# tms9918.net
KiCad netlist of a schematic drawn in EAGLE
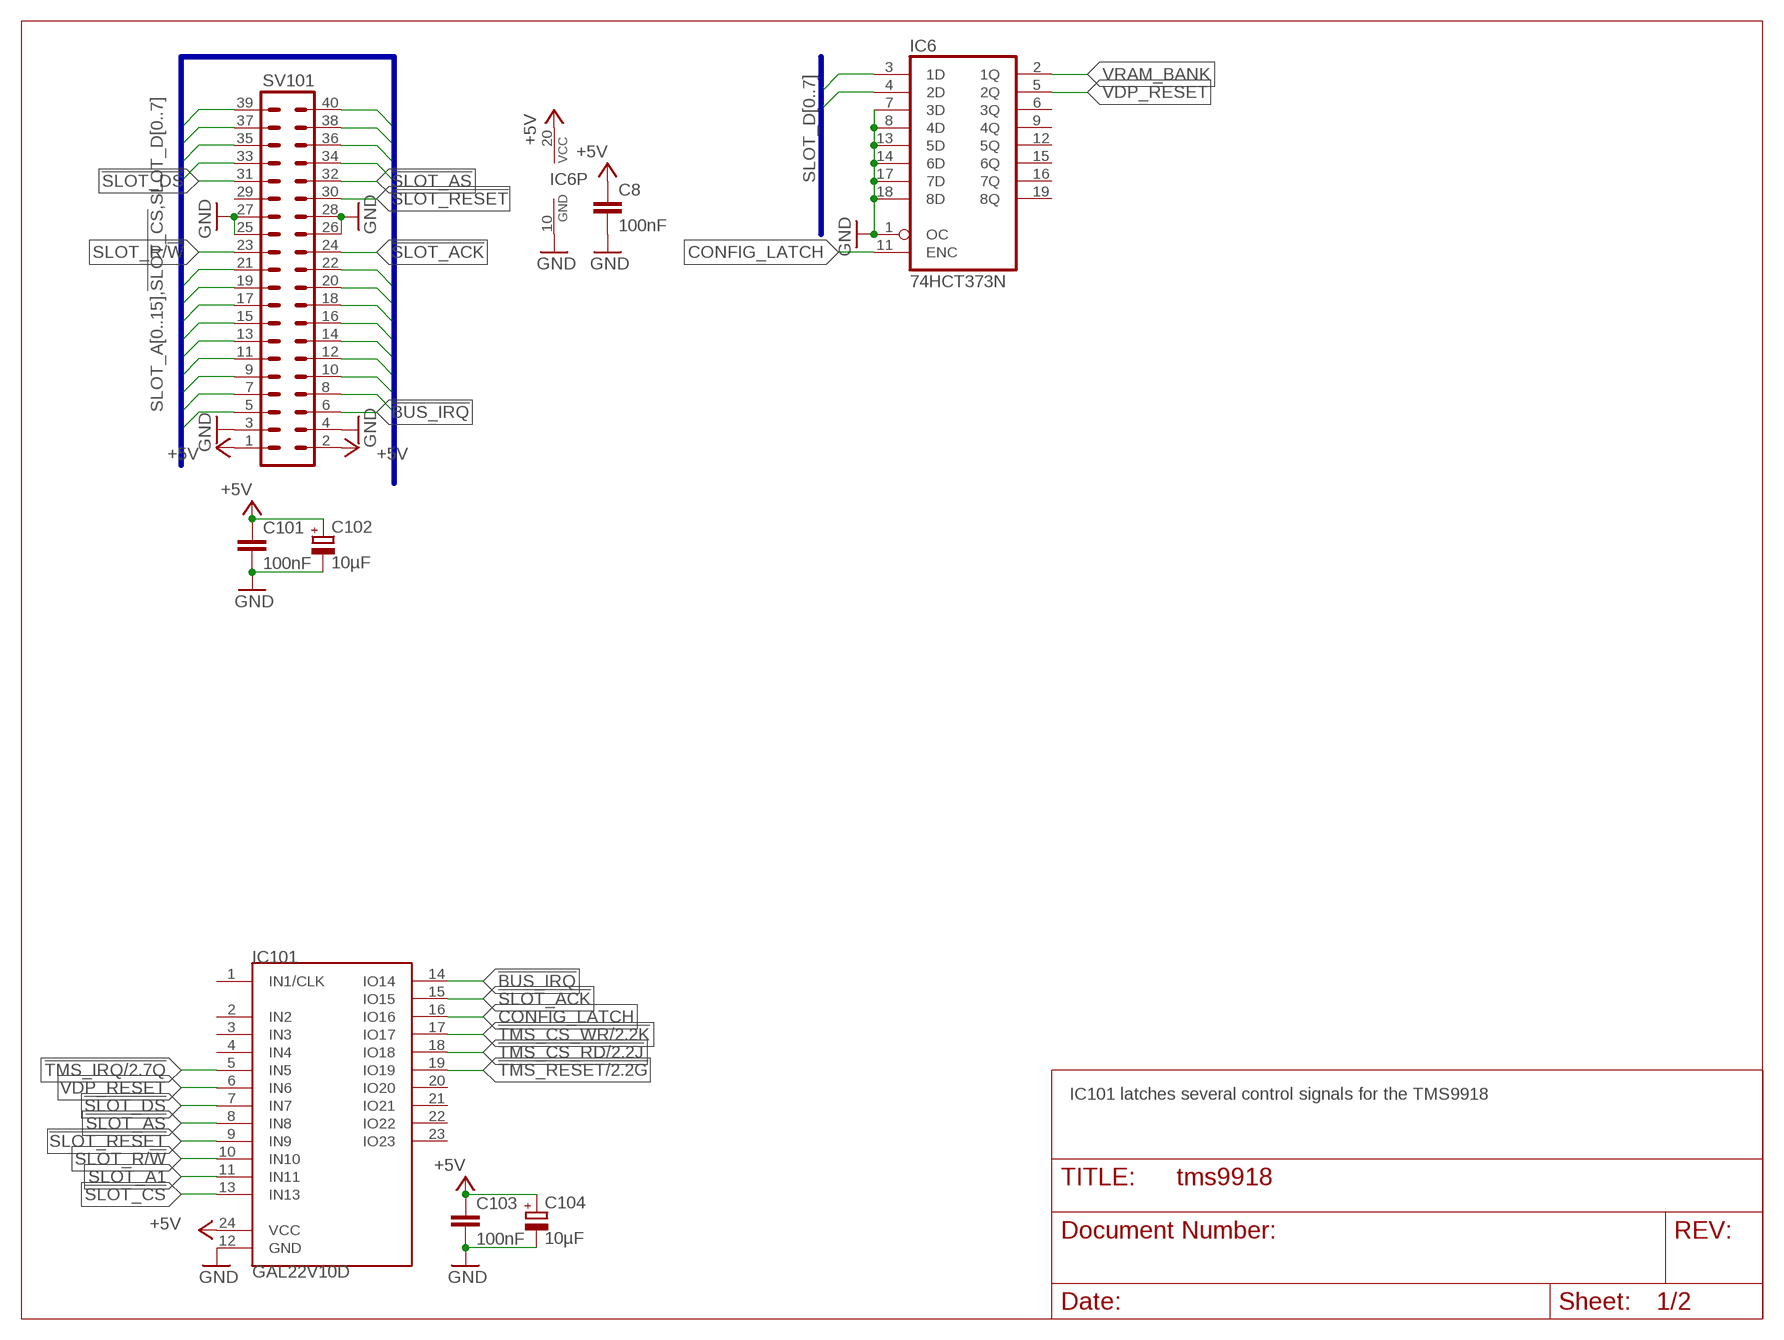
[diagram p0: schematic, sheet 1]
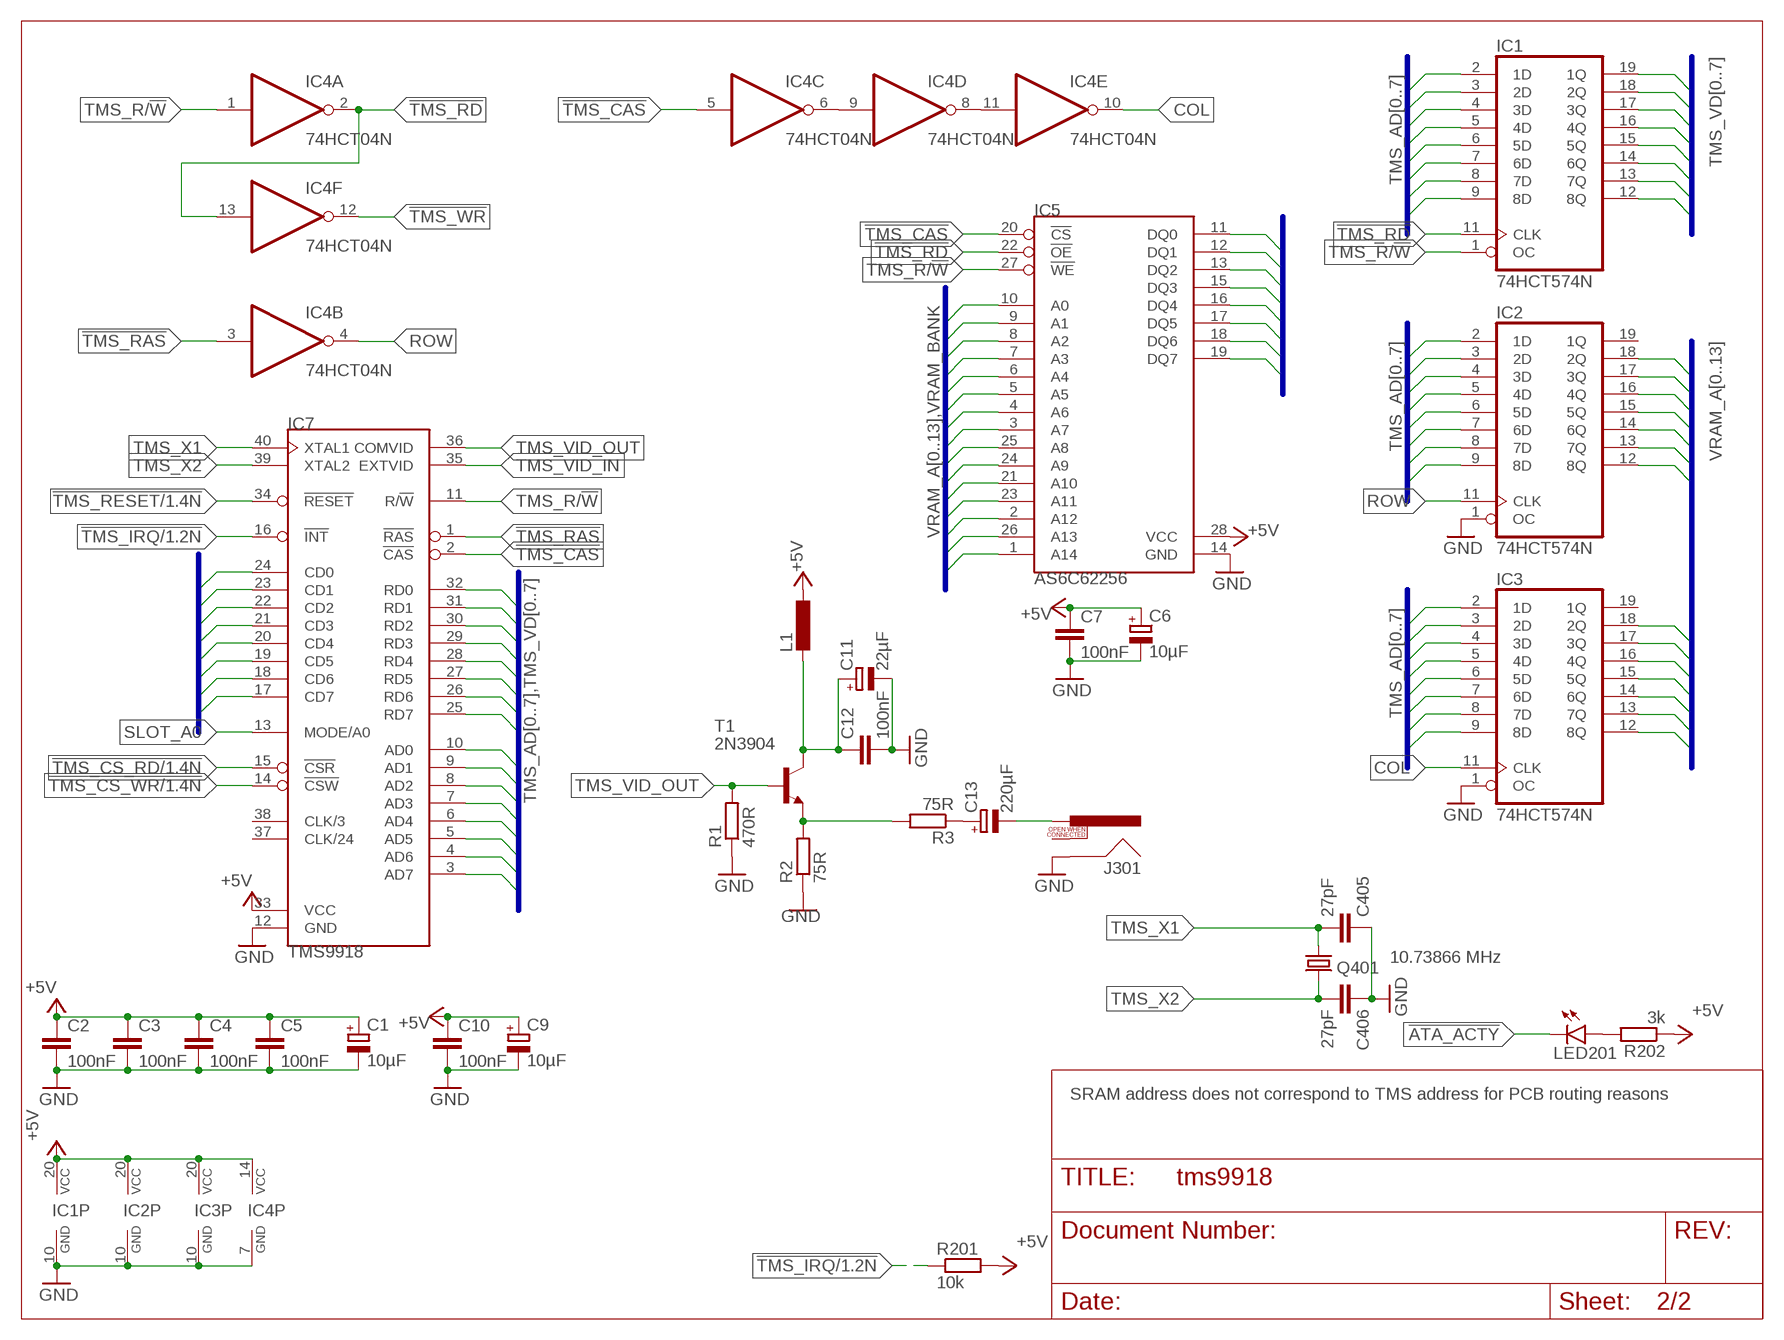
[diagram p1: schematic, sheet 2]

(export (version "E")
  (design (tool "Eeschema 10.0.6"))
  (components
    (comp (ref "C8")
      (value "100nF")
      (footprint "eagle-import:C0805")
      (libsource (lib "eagle-import") (part "C-EUC0805"))
    )
    (comp (ref "C101")
      (value "100nF")
      (footprint "eagle-import:C0805")
      (libsource (lib "eagle-import") (part "C-EUC0805"))
    )
    (comp (ref "C102")
      (value "10µF")
      (footprint "eagle-import:SMC_B")
      (libsource (lib "eagle-import") (part "CPOL-EUSMCB"))
    )
    (comp (ref "C103")
      (value "100nF")
      (footprint "eagle-import:C0805")
      (libsource (lib "eagle-import") (part "C-EUC0805"))
    )
    (comp (ref "C104")
      (value "10µF")
      (footprint "eagle-import:SMC_B")
      (libsource (lib "eagle-import") (part "CPOL-EUSMCB"))
    )
    (comp (ref "IC6")
      (value "74HCT373N")
      (footprint "eagle-import:DIL20")
      (fields (field (name "MOUSER") "595-SN74HCT373N") (field (name "MOUSER_SOCKET") "575-1104732041001000"))
      (libsource (lib "eagle-import") (part "74373NHCT"))
    )
    (comp (ref "IC101")
      (value "GAL22V10D")
      (footprint "eagle-import:DIL24S")
      (libsource (lib "eagle-import") (part "GAL22V10DIP24"))
    )
    (comp (ref "SV101")
      (value "MA20-2W")
      (footprint "eagle-import:MA20-2W")
      (libsource (lib "eagle-import") (part "MA20-2W"))
    )
    (comp (ref "C1")
      (value "10µF")
      (footprint "eagle-import:SMC_B")
      (libsource (lib "eagle-import") (part "CPOL-EUSMCB"))
    )
    (comp (ref "C2")
      (value "100nF")
      (footprint "eagle-import:C0805")
      (libsource (lib "eagle-import") (part "C-EUC0805"))
    )
    (comp (ref "C3")
      (value "100nF")
      (footprint "eagle-import:C0805")
      (libsource (lib "eagle-import") (part "C-EUC0805"))
    )
    (comp (ref "C4")
      (value "100nF")
      (footprint "eagle-import:C0805")
      (libsource (lib "eagle-import") (part "C-EUC0805"))
    )
    (comp (ref "C5")
      (value "100nF")
      (footprint "eagle-import:C0805")
      (libsource (lib "eagle-import") (part "C-EUC0805"))
    )
    (comp (ref "C6")
      (value "10µF")
      (footprint "eagle-import:SMC_B")
      (libsource (lib "eagle-import") (part "CPOL-EUSMCB"))
    )
    (comp (ref "C7")
      (value "100nF")
      (footprint "eagle-import:C0805")
      (libsource (lib "eagle-import") (part "C-EUC0805"))
    )
    (comp (ref "C9")
      (value "10µF")
      (footprint "eagle-import:SMC_B")
      (libsource (lib "eagle-import") (part "CPOL-EUSMCB"))
    )
    (comp (ref "C10")
      (value "100nF")
      (footprint "eagle-import:C0805")
      (libsource (lib "eagle-import") (part "C-EUC0805"))
    )
    (comp (ref "C11")
      (value "22µF")
      (footprint "eagle-import:E2-5")
      (libsource (lib "eagle-import") (part "CPOL-EUE2-5"))
    )
    (comp (ref "C12")
      (value "100nF")
      (footprint "eagle-import:C0805")
      (libsource (lib "eagle-import") (part "C-EUC0805"))
    )
    (comp (ref "C13")
      (value "220µF")
      (footprint "eagle-import:E2,5-7")
      (libsource (lib "eagle-import") (part "CPOL-EUE2.5-7"))
    )
    (comp (ref "C405")
      (value "27pF")
      (footprint "eagle-import:C0805")
      (libsource (lib "eagle-import") (part "C-EUC0805"))
    )
    (comp (ref "C406")
      (value "27pF")
      (footprint "eagle-import:C0805")
      (libsource (lib "eagle-import") (part "C-EUC0805"))
    )
    (comp (ref "IC1")
      (value "74HCT574N")
      (footprint "eagle-import:DIL20")
      (fields (field (name "MOUSER") "595-SN74HCT574N") (field (name "MOUSER_SOCKET") "575-1104732041001000"))
      (libsource (lib "eagle-import") (part "74574NHCT"))
    )
    (comp (ref "IC2")
      (value "74HCT574N")
      (footprint "eagle-import:DIL20")
      (fields (field (name "MOUSER") "595-SN74HCT574N") (field (name "MOUSER_SOCKET") "575-1104732041001000"))
      (libsource (lib "eagle-import") (part "74574NHCT"))
    )
    (comp (ref "IC3")
      (value "74HCT574N")
      (footprint "eagle-import:DIL20")
      (fields (field (name "MOUSER") "595-SN74HCT574N") (field (name "MOUSER_SOCKET") "575-1104732041001000"))
      (libsource (lib "eagle-import") (part "74574NHCT"))
    )
    (comp (ref "IC4")
      (value "74HCT04N")
      (footprint "eagle-import:DIL14")
      (fields (field (name "MOUSER") "595-SN74HCT04N") (field (name "MOUSER_SOCKET") "575-1104731441001000"))
      (libsource (lib "eagle-import") (part "7404NHCT"))
    )
    (comp (ref "IC5")
      (value "AS6C62256")
      (footprint "eagle-import:DIL28-6")
      (libsource (lib "eagle-import") (part "AS6C62256"))
    )
    (comp (ref "IC7")
      (value "TMS9918")
      (footprint "eagle-import:DIL40")
      (libsource (lib "eagle-import") (part "TMS9918"))
    )
    (comp (ref "J301")
      (value "RCALOCK")
      (footprint "eagle-import:RCA_LOCK")
      (libsource (lib "eagle-import") (part "RCALOCK"))
    )
    (comp (ref "L1")
      (value "L-EUL2012C")
      (footprint "eagle-import:L2012C")
      (libsource (lib "eagle-import") (part "L-EUL2012C"))
    )
    (comp (ref "LED201")
      (value "LEDCHIPLED_1206")
      (footprint "eagle-import:CHIPLED_1206")
      (libsource (lib "eagle-import") (part "LEDCHIPLED_1206"))
    )
    (comp (ref "Q401")
      (value "10.73866 MHz")
      (footprint "eagle-import:HC49_S")
      (libsource (lib "eagle-import") (part "CRYSTALHC49S"))
    )
    (comp (ref "R1")
      (value "470R")
      (footprint "eagle-import:R2012")
      (libsource (lib "eagle-import") (part "R-EU_R2012"))
    )
    (comp (ref "R2")
      (value "75R")
      (footprint "eagle-import:R2012")
      (libsource (lib "eagle-import") (part "R-EU_R2012"))
    )
    (comp (ref "R3")
      (value "75R")
      (footprint "eagle-import:R2012")
      (libsource (lib "eagle-import") (part "R-EU_R2012"))
    )
    (comp (ref "R201")
      (value "10k")
      (footprint "eagle-import:R2012")
      (libsource (lib "eagle-import") (part "R-EU_R2012"))
    )
    (comp (ref "R202")
      (value "3k")
      (footprint "eagle-import:R2012")
      (libsource (lib "eagle-import") (part "R-EU_R2012"))
    )
    (comp (ref "T1")
      (value "2N3904")
      (footprint "eagle-import:TO92")
      (libsource (lib "eagle-import") (part "2N3904"))
    )
  )
  (nets
    (net (code "1") (name "+5V") (class "Default")
      (node (ref "C1") (pin "+") (pinfunction "+_+") (pintype "passive"))
      (node (ref "C10") (pin "1") (pinfunction "1_1") (pintype "passive"))
      (node (ref "C101") (pin "1") (pinfunction "1_1") (pintype "passive"))
      (node (ref "C102") (pin "+") (pinfunction "+_+") (pintype "passive"))
      (node (ref "C103") (pin "1") (pinfunction "1_1") (pintype "passive"))
      (node (ref "C104") (pin "+") (pinfunction "+_+") (pintype "passive"))
      (node (ref "C2") (pin "1") (pinfunction "1_1") (pintype "passive"))
      (node (ref "C3") (pin "1") (pinfunction "1_1") (pintype "passive"))
      (node (ref "C4") (pin "1") (pinfunction "1_1") (pintype "passive"))
      (node (ref "C5") (pin "1") (pinfunction "1_1") (pintype "passive"))
      (node (ref "C6") (pin "+") (pinfunction "+_+") (pintype "passive"))
      (node (ref "C7") (pin "1") (pinfunction "1_1") (pintype "passive"))
      (node (ref "C8") (pin "1") (pinfunction "1_1") (pintype "passive"))
      (node (ref "C9") (pin "+") (pinfunction "+_+") (pintype "passive"))
      (node (ref "IC1") (pin "20") (pinfunction "VCC_20") (pintype "power_in"))
      (node (ref "IC101") (pin "24") (pinfunction "VCC_24") (pintype "power_in"))
      (node (ref "IC2") (pin "20") (pinfunction "VCC_20") (pintype "power_in"))
      (node (ref "IC3") (pin "20") (pinfunction "VCC_20") (pintype "power_in"))
      (node (ref "IC4") (pin "14") (pinfunction "VCC_14") (pintype "power_in"))
      (node (ref "IC5") (pin "28") (pinfunction "VCC_28") (pintype "power_in"))
      (node (ref "IC6") (pin "20") (pinfunction "VCC_20") (pintype "power_in"))
      (node (ref "IC7") (pin "33") (pinfunction "VCC_33") (pintype "power_in"))
      (node (ref "L1") (pin "1") (pinfunction "1_1") (pintype "passive"))
      (node (ref "R201") (pin "2") (pinfunction "2_2") (pintype "passive"))
      (node (ref "R202") (pin "1") (pinfunction "1_1") (pintype "passive"))
      (node (ref "SV101") (pin "1") (pinfunction "1_1") (pintype "passive"))
      (node (ref "SV101") (pin "2") (pinfunction "2_2") (pintype "passive"))
    )
    (net (code "9") (name "COL") (class "Default")
      (node (ref "IC3") (pin "11") (pinfunction "CLK_11") (pintype "input"))
      (node (ref "IC4") (pin "10") (pinfunction "O_10") (pintype "output"))
    )
    (net (code "10") (name "CONFIG_LATCH") (class "Default")
      (node (ref "IC101") (pin "16") (pinfunction "IO16_16") (pintype "bidirectional"))
      (node (ref "IC6") (pin "11") (pinfunction "ENC_11") (pintype "input"))
    )
    (net (code "11") (name "GND") (class "Default")
      (node (ref "C1") (pin "-") (pinfunction "-_-") (pintype "passive"))
      (node (ref "C10") (pin "2") (pinfunction "2_2") (pintype "passive"))
      (node (ref "C101") (pin "2") (pinfunction "2_2") (pintype "passive"))
      (node (ref "C102") (pin "-") (pinfunction "-_-") (pintype "passive"))
      (node (ref "C103") (pin "2") (pinfunction "2_2") (pintype "passive"))
      (node (ref "C104") (pin "-") (pinfunction "-_-") (pintype "passive"))
      (node (ref "C11") (pin "-") (pinfunction "-_-") (pintype "passive"))
      (node (ref "C12") (pin "2") (pinfunction "2_2") (pintype "passive"))
      (node (ref "C2") (pin "2") (pinfunction "2_2") (pintype "passive"))
      (node (ref "C3") (pin "2") (pinfunction "2_2") (pintype "passive"))
      (node (ref "C4") (pin "2") (pinfunction "2_2") (pintype "passive"))
      (node (ref "C405") (pin "1") (pinfunction "1_1") (pintype "passive"))
      (node (ref "C406") (pin "1") (pinfunction "1_1") (pintype "passive"))
      (node (ref "C5") (pin "2") (pinfunction "2_2") (pintype "passive"))
      (node (ref "C6") (pin "-") (pinfunction "-_-") (pintype "passive"))
      (node (ref "C7") (pin "2") (pinfunction "2_2") (pintype "passive"))
      (node (ref "C8") (pin "2") (pinfunction "2_2") (pintype "passive"))
      (node (ref "C9") (pin "-") (pinfunction "-_-") (pintype "passive"))
      (node (ref "IC1") (pin "10") (pinfunction "GND_10") (pintype "power_in"))
      (node (ref "IC101") (pin "12") (pinfunction "GND_12") (pintype "power_in"))
      (node (ref "IC2") (pin "1") (pinfunction "OC_1") (pintype "input"))
      (node (ref "IC2") (pin "10") (pinfunction "GND_10") (pintype "power_in"))
      (node (ref "IC3") (pin "1") (pinfunction "OC_1") (pintype "input"))
      (node (ref "IC3") (pin "10") (pinfunction "GND_10") (pintype "power_in"))
      (node (ref "IC4") (pin "7") (pinfunction "GND_7") (pintype "power_in"))
      (node (ref "IC5") (pin "14") (pinfunction "GND_14") (pintype "power_in"))
      (node (ref "IC6") (pin "1") (pinfunction "OC_1") (pintype "input"))
      (node (ref "IC6") (pin "10") (pinfunction "GND_10") (pintype "power_in"))
      (node (ref "IC6") (pin "13") (pinfunction "5D_13") (pintype "input"))
      (node (ref "IC6") (pin "14") (pinfunction "6D_14") (pintype "input"))
      (node (ref "IC6") (pin "17") (pinfunction "7D_17") (pintype "input"))
      (node (ref "IC6") (pin "18") (pinfunction "8D_18") (pintype "input"))
      (node (ref "IC6") (pin "7") (pinfunction "3D_7") (pintype "input"))
      (node (ref "IC6") (pin "8") (pinfunction "4D_8") (pintype "input"))
      (node (ref "IC7") (pin "12") (pinfunction "GND_12") (pintype "power_in"))
      (node (ref "J301") (pin "SHELL") (pinfunction "SHELL_SHELL") (pintype "bidirectional"))
      (node (ref "R1") (pin "1") (pinfunction "1_1") (pintype "passive"))
      (node (ref "R2") (pin "1") (pinfunction "1_1") (pintype "passive"))
      (node (ref "SV101") (pin "25") (pinfunction "25_25") (pintype "passive"))
      (node (ref "SV101") (pin "26") (pinfunction "26_26") (pintype "passive"))
      (node (ref "SV101") (pin "27") (pinfunction "27_27") (pintype "passive"))
      (node (ref "SV101") (pin "28") (pinfunction "28_28") (pintype "passive"))
      (node (ref "SV101") (pin "3") (pinfunction "3_3") (pintype "passive"))
      (node (ref "SV101") (pin "4") (pinfunction "4_4") (pintype "passive"))
    )
    (net (code "12") (name "Net-(C13-Pad+)") (class "Default")
      (node (ref "C13") (pin "+") (pinfunction "+_+") (pintype "passive"))
      (node (ref "R3") (pin "1") (pinfunction "1_1") (pintype "passive"))
    )
    (net (code "13") (name "Net-(C13-Pad-)") (class "Default")
      (node (ref "C13") (pin "-") (pinfunction "-_-") (pintype "passive"))
      (node (ref "J301") (pin "PIN") (pinfunction "PIN_PIN") (pintype "bidirectional"))
    )
    (net (code "14") (name "Net-(IC4C-O)") (class "Default")
      (node (ref "IC4") (pin "6") (pinfunction "O_6") (pintype "output"))
      (node (ref "IC4") (pin "9") (pinfunction "I_9") (pintype "input"))
    )
    (net (code "15") (name "Net-(IC4D-O)") (class "Default")
      (node (ref "IC4") (pin "11") (pinfunction "I_11") (pintype "input"))
      (node (ref "IC4") (pin "8") (pinfunction "O_8") (pintype "output"))
    )
    (net (code "16") (name "Net-(LED201-PadA)") (class "Default")
      (node (ref "LED201") (pin "A") (pinfunction "A_A") (pintype "passive"))
      (node (ref "R202") (pin "2") (pinfunction "2_2") (pintype "passive"))
    )
    (net (code "17") (name "Net-(T1-C)") (class "Default")
      (node (ref "C11") (pin "+") (pinfunction "+_+") (pintype "passive"))
      (node (ref "C12") (pin "1") (pinfunction "1_1") (pintype "passive"))
      (node (ref "L1") (pin "2") (pinfunction "2_2") (pintype "passive"))
      (node (ref "T1") (pin "1") (pinfunction "C_1") (pintype "passive"))
    )
    (net (code "18") (name "Net-(T1-E)") (class "Default")
      (node (ref "R2") (pin "2") (pinfunction "2_2") (pintype "passive"))
      (node (ref "R3") (pin "2") (pinfunction "2_2") (pintype "passive"))
      (node (ref "T1") (pin "3") (pinfunction "E_3") (pintype "passive"))
    )
    (net (code "19") (name "ROW") (class "Default")
      (node (ref "IC2") (pin "11") (pinfunction "CLK_11") (pintype "input"))
      (node (ref "IC4") (pin "4") (pinfunction "O_4") (pintype "output"))
    )
    (net (code "20") (name "SLOT_A0") (class "Default")
      (node (ref "IC7") (pin "13") (pinfunction "MODE/A0_13") (pintype "input"))
      (node (ref "SV101") (pin "12") (pinfunction "12_12") (pintype "passive"))
    )
    (net (code "21") (name "SLOT_A1") (class "Default")
      (node (ref "IC101") (pin "11") (pinfunction "IN11_11") (pintype "input"))
      (node (ref "SV101") (pin "10") (pinfunction "10_10") (pintype "passive"))
    )
    (net (code "22") (name "SLOT_D0") (class "Default")
      (node (ref "IC6") (pin "3") (pinfunction "1D_3") (pintype "input"))
      (node (ref "IC7") (pin "17") (pinfunction "CD7_17") (pintype "bidirectional"))
      (node (ref "SV101") (pin "35") (pinfunction "35_35") (pintype "passive"))
    )
    (net (code "23") (name "SLOT_D1") (class "Default")
      (node (ref "IC6") (pin "4") (pinfunction "2D_4") (pintype "input"))
      (node (ref "IC7") (pin "18") (pinfunction "CD6_18") (pintype "bidirectional"))
      (node (ref "SV101") (pin "37") (pinfunction "37_37") (pintype "passive"))
    )
    (net (code "24") (name "SLOT_D2") (class "Default")
      (node (ref "IC7") (pin "19") (pinfunction "CD5_19") (pintype "bidirectional"))
      (node (ref "SV101") (pin "39") (pinfunction "39_39") (pintype "passive"))
    )
    (net (code "25") (name "SLOT_D3") (class "Default")
      (node (ref "IC7") (pin "20") (pinfunction "CD4_20") (pintype "bidirectional"))
      (node (ref "SV101") (pin "40") (pinfunction "40_40") (pintype "passive"))
    )
    (net (code "26") (name "SLOT_D4") (class "Default")
      (node (ref "IC7") (pin "21") (pinfunction "CD3_21") (pintype "bidirectional"))
      (node (ref "SV101") (pin "38") (pinfunction "38_38") (pintype "passive"))
    )
    (net (code "27") (name "SLOT_D5") (class "Default")
      (node (ref "IC7") (pin "22") (pinfunction "CD2_22") (pintype "bidirectional"))
      (node (ref "SV101") (pin "36") (pinfunction "36_36") (pintype "passive"))
    )
    (net (code "28") (name "SLOT_D6") (class "Default")
      (node (ref "IC7") (pin "23") (pinfunction "CD1_23") (pintype "bidirectional"))
      (node (ref "SV101") (pin "34") (pinfunction "34_34") (pintype "passive"))
    )
    (net (code "29") (name "SLOT_D7") (class "Default")
      (node (ref "IC7") (pin "24") (pinfunction "CD0_24") (pintype "bidirectional"))
      (node (ref "SV101") (pin "33") (pinfunction "33_33") (pintype "passive"))
    )
    (net (code "30") (name "SLOT_R{slash}~{W}") (class "Default")
      (node (ref "IC101") (pin "10") (pinfunction "IN10_10") (pintype "input"))
      (node (ref "SV101") (pin "23") (pinfunction "23_23") (pintype "passive"))
    )
    (net (code "31") (name "TMS_AD0") (class "Default")
      (node (ref "IC1") (pin "2") (pinfunction "1D_2") (pintype "input"))
      (node (ref "IC2") (pin "9") (pinfunction "8D_9") (pintype "input"))
      (node (ref "IC3") (pin "9") (pinfunction "8D_9") (pintype "input"))
      (node (ref "IC7") (pin "10") (pinfunction "AD0_10") (pintype "input"))
    )
    (net (code "32") (name "TMS_AD1") (class "Default")
      (node (ref "IC1") (pin "3") (pinfunction "2D_3") (pintype "input"))
      (node (ref "IC2") (pin "8") (pinfunction "7D_8") (pintype "input"))
      (node (ref "IC3") (pin "8") (pinfunction "7D_8") (pintype "input"))
      (node (ref "IC7") (pin "9") (pinfunction "AD1_9") (pintype "input"))
    )
    (net (code "33") (name "TMS_AD2") (class "Default")
      (node (ref "IC1") (pin "4") (pinfunction "3D_4") (pintype "input"))
      (node (ref "IC2") (pin "7") (pinfunction "6D_7") (pintype "input"))
      (node (ref "IC3") (pin "7") (pinfunction "6D_7") (pintype "input"))
      (node (ref "IC7") (pin "8") (pinfunction "AD2_8") (pintype "input"))
    )
    (net (code "34") (name "TMS_AD3") (class "Default")
      (node (ref "IC1") (pin "5") (pinfunction "4D_5") (pintype "input"))
      (node (ref "IC2") (pin "6") (pinfunction "5D_6") (pintype "input"))
      (node (ref "IC3") (pin "6") (pinfunction "5D_6") (pintype "input"))
      (node (ref "IC7") (pin "7") (pinfunction "AD3_7") (pintype "input"))
    )
    (net (code "35") (name "TMS_AD4") (class "Default")
      (node (ref "IC1") (pin "6") (pinfunction "5D_6") (pintype "input"))
      (node (ref "IC2") (pin "5") (pinfunction "4D_5") (pintype "input"))
      (node (ref "IC3") (pin "5") (pinfunction "4D_5") (pintype "input"))
      (node (ref "IC7") (pin "6") (pinfunction "AD4_6") (pintype "input"))
    )
    (net (code "36") (name "TMS_AD5") (class "Default")
      (node (ref "IC1") (pin "7") (pinfunction "6D_7") (pintype "input"))
      (node (ref "IC2") (pin "4") (pinfunction "3D_4") (pintype "input"))
      (node (ref "IC3") (pin "4") (pinfunction "3D_4") (pintype "input"))
      (node (ref "IC7") (pin "5") (pinfunction "AD5_5") (pintype "input"))
    )
    (net (code "37") (name "TMS_AD6") (class "Default")
      (node (ref "IC1") (pin "8") (pinfunction "7D_8") (pintype "input"))
      (node (ref "IC2") (pin "3") (pinfunction "2D_3") (pintype "input"))
      (node (ref "IC3") (pin "3") (pinfunction "2D_3") (pintype "input"))
      (node (ref "IC7") (pin "4") (pinfunction "AD6_4") (pintype "input"))
    )
    (net (code "38") (name "TMS_AD7") (class "Default")
      (node (ref "IC1") (pin "9") (pinfunction "8D_9") (pintype "input"))
      (node (ref "IC2") (pin "2") (pinfunction "1D_2") (pintype "input"))
      (node (ref "IC3") (pin "2") (pinfunction "1D_2") (pintype "input"))
      (node (ref "IC7") (pin "3") (pinfunction "AD7_3") (pintype "input"))
    )
    (net (code "39") (name "TMS_R{slash}~{W}") (class "Default")
      (node (ref "IC1") (pin "1") (pinfunction "OC_1") (pintype "input"))
      (node (ref "IC4") (pin "1") (pinfunction "I_1") (pintype "input"))
      (node (ref "IC5") (pin "27") (pinfunction "~{WE}_27") (pintype "input"))
      (node (ref "IC7") (pin "11") (pinfunction "R/~{W}_11") (pintype "output"))
    )
    (net (code "40") (name "TMS_VD0") (class "Default")
      (node (ref "IC1") (pin "19") (pinfunction "1Q_19") (pintype "tri_state"))
      (node (ref "IC5") (pin "11") (pinfunction "DQ0_11") (pintype "bidirectional"))
      (node (ref "IC7") (pin "32") (pinfunction "RD0_32") (pintype "input"))
    )
    (net (code "41") (name "TMS_VD1") (class "Default")
      (node (ref "IC1") (pin "18") (pinfunction "2Q_18") (pintype "tri_state"))
      (node (ref "IC5") (pin "12") (pinfunction "DQ1_12") (pintype "bidirectional"))
      (node (ref "IC7") (pin "31") (pinfunction "RD1_31") (pintype "input"))
    )
    (net (code "42") (name "TMS_VD2") (class "Default")
      (node (ref "IC1") (pin "17") (pinfunction "3Q_17") (pintype "tri_state"))
      (node (ref "IC5") (pin "13") (pinfunction "DQ2_13") (pintype "bidirectional"))
      (node (ref "IC7") (pin "30") (pinfunction "RD2_30") (pintype "input"))
    )
    (net (code "43") (name "TMS_VD3") (class "Default")
      (node (ref "IC1") (pin "16") (pinfunction "4Q_16") (pintype "tri_state"))
      (node (ref "IC5") (pin "15") (pinfunction "DQ3_15") (pintype "bidirectional"))
      (node (ref "IC7") (pin "29") (pinfunction "RD3_29") (pintype "input"))
    )
    (net (code "44") (name "TMS_VD4") (class "Default")
      (node (ref "IC1") (pin "15") (pinfunction "5Q_15") (pintype "tri_state"))
      (node (ref "IC5") (pin "16") (pinfunction "DQ4_16") (pintype "bidirectional"))
      (node (ref "IC7") (pin "28") (pinfunction "RD4_28") (pintype "input"))
    )
    (net (code "45") (name "TMS_VD5") (class "Default")
      (node (ref "IC1") (pin "14") (pinfunction "6Q_14") (pintype "tri_state"))
      (node (ref "IC5") (pin "17") (pinfunction "DQ5_17") (pintype "bidirectional"))
      (node (ref "IC7") (pin "27") (pinfunction "RD5_27") (pintype "input"))
    )
    (net (code "46") (name "TMS_VD6") (class "Default")
      (node (ref "IC1") (pin "13") (pinfunction "7Q_13") (pintype "tri_state"))
      (node (ref "IC5") (pin "18") (pinfunction "DQ6_18") (pintype "bidirectional"))
      (node (ref "IC7") (pin "26") (pinfunction "RD6_26") (pintype "input"))
    )
    (net (code "47") (name "TMS_VD7") (class "Default")
      (node (ref "IC1") (pin "12") (pinfunction "8Q_12") (pintype "tri_state"))
      (node (ref "IC5") (pin "19") (pinfunction "DQ7_19") (pintype "bidirectional"))
      (node (ref "IC7") (pin "25") (pinfunction "RD7_25") (pintype "input"))
    )
    (net (code "48") (name "TMS_VID_IN") (class "Default")
      (node (ref "IC7") (pin "35") (pinfunction "EXTVID_35") (pintype "input"))
    )
    (net (code "49") (name "TMS_VID_OUT") (class "Default")
      (node (ref "IC7") (pin "36") (pinfunction "COMVID_36") (pintype "output"))
      (node (ref "R1") (pin "2") (pinfunction "2_2") (pintype "passive"))
      (node (ref "T1") (pin "2") (pinfunction "B_2") (pintype "passive"))
    )
    (net (code "50") (name "TMS_X1") (class "Default")
      (node (ref "C405") (pin "2") (pinfunction "2_2") (pintype "passive"))
      (node (ref "IC7") (pin "40") (pinfunction "XTAL1_40") (pintype "passive"))
      (node (ref "Q401") (pin "1") (pinfunction "1_1") (pintype "passive"))
    )
    (net (code "51") (name "TMS_X2") (class "Default")
      (node (ref "C406") (pin "2") (pinfunction "2_2") (pintype "passive"))
      (node (ref "IC7") (pin "39") (pinfunction "XTAL2_39") (pintype "passive"))
      (node (ref "Q401") (pin "2") (pinfunction "2_2") (pintype "passive"))
    )
    (net (code "52") (name "VDP_RESET") (class "Default")
      (node (ref "IC101") (pin "6") (pinfunction "IN6_6") (pintype "input"))
      (node (ref "IC6") (pin "5") (pinfunction "2Q_5") (pintype "tri_state"))
    )
    (net (code "53") (name "VRAM_A0") (class "Default")
      (node (ref "IC2") (pin "12") (pinfunction "8Q_12") (pintype "tri_state"))
      (node (ref "IC5") (pin "10") (pinfunction "A0_10") (pintype "input"))
    )
    (net (code "54") (name "VRAM_A1") (class "Default")
      (node (ref "IC2") (pin "13") (pinfunction "7Q_13") (pintype "tri_state"))
      (node (ref "IC5") (pin "9") (pinfunction "A1_9") (pintype "input"))
    )
    (net (code "55") (name "VRAM_A2") (class "Default")
      (node (ref "IC2") (pin "14") (pinfunction "6Q_14") (pintype "tri_state"))
      (node (ref "IC5") (pin "8") (pinfunction "A2_8") (pintype "input"))
    )
    (net (code "56") (name "VRAM_A3") (class "Default")
      (node (ref "IC2") (pin "15") (pinfunction "5Q_15") (pintype "tri_state"))
      (node (ref "IC5") (pin "7") (pinfunction "A3_7") (pintype "input"))
    )
    (net (code "57") (name "VRAM_A4") (class "Default")
      (node (ref "IC2") (pin "16") (pinfunction "4Q_16") (pintype "tri_state"))
      (node (ref "IC5") (pin "6") (pinfunction "A4_6") (pintype "input"))
    )
    (net (code "58") (name "VRAM_A5") (class "Default")
      (node (ref "IC2") (pin "17") (pinfunction "3Q_17") (pintype "tri_state"))
      (node (ref "IC5") (pin "5") (pinfunction "A5_5") (pintype "input"))
    )
    (net (code "59") (name "VRAM_A6") (class "Default")
      (node (ref "IC2") (pin "18") (pinfunction "2Q_18") (pintype "tri_state"))
      (node (ref "IC5") (pin "4") (pinfunction "A6_4") (pintype "input"))
    )
    (net (code "60") (name "VRAM_A7") (class "Default")
      (node (ref "IC3") (pin "17") (pinfunction "3Q_17") (pintype "tri_state"))
      (node (ref "IC5") (pin "3") (pinfunction "A7_3") (pintype "input"))
    )
    (net (code "61") (name "VRAM_A8") (class "Default")
      (node (ref "IC3") (pin "15") (pinfunction "5Q_15") (pintype "tri_state"))
      (node (ref "IC5") (pin "25") (pinfunction "A8_25") (pintype "input"))
    )
    (net (code "62") (name "VRAM_A9") (class "Default")
      (node (ref "IC3") (pin "14") (pinfunction "6Q_14") (pintype "tri_state"))
      (node (ref "IC5") (pin "24") (pinfunction "A9_24") (pintype "input"))
    )
    (net (code "63") (name "VRAM_A10") (class "Default")
      (node (ref "IC3") (pin "12") (pinfunction "8Q_12") (pintype "tri_state"))
      (node (ref "IC5") (pin "21") (pinfunction "A10_21") (pintype "input"))
    )
    (net (code "64") (name "VRAM_A11") (class "Default")
      (node (ref "IC3") (pin "13") (pinfunction "7Q_13") (pintype "tri_state"))
      (node (ref "IC5") (pin "23") (pinfunction "A11_23") (pintype "input"))
    )
    (net (code "65") (name "VRAM_A12") (class "Default")
      (node (ref "IC3") (pin "18") (pinfunction "2Q_18") (pintype "tri_state"))
      (node (ref "IC5") (pin "2") (pinfunction "A12_2") (pintype "input"))
    )
    (net (code "66") (name "VRAM_A13") (class "Default")
      (node (ref "IC3") (pin "16") (pinfunction "4Q_16") (pintype "tri_state"))
      (node (ref "IC5") (pin "26") (pinfunction "A13_26") (pintype "input"))
    )
    (net (code "67") (name "VRAM_BANK") (class "Default")
      (node (ref "IC5") (pin "1") (pinfunction "A14_1") (pintype "input"))
      (node (ref "IC6") (pin "2") (pinfunction "1Q_2") (pintype "tri_state"))
    )
    (net (code "68") (name "unconnected-(IC2A-1Q-Pad19)") (class "Default")
      (node (ref "IC2") (pin "19") (pinfunction "1Q_19") (pintype "tri_state"))
    )
    (net (code "69") (name "unconnected-(IC3A-1Q-Pad19)") (class "Default")
      (node (ref "IC3") (pin "19") (pinfunction "1Q_19") (pintype "tri_state"))
    )
    (net (code "70") (name "unconnected-(IC6A-3Q-Pad6)") (class "Default")
      (node (ref "IC6") (pin "6") (pinfunction "3Q_6") (pintype "tri_state"))
    )
    (net (code "71") (name "unconnected-(IC6A-4Q-Pad9)") (class "Default")
      (node (ref "IC6") (pin "9") (pinfunction "4Q_9") (pintype "tri_state"))
    )
    (net (code "72") (name "unconnected-(IC6A-5Q-Pad12)") (class "Default")
      (node (ref "IC6") (pin "12") (pinfunction "5Q_12") (pintype "tri_state"))
    )
    (net (code "73") (name "unconnected-(IC6A-6Q-Pad15)") (class "Default")
      (node (ref "IC6") (pin "15") (pinfunction "6Q_15") (pintype "tri_state"))
    )
    (net (code "74") (name "unconnected-(IC6A-7Q-Pad16)") (class "Default")
      (node (ref "IC6") (pin "16") (pinfunction "7Q_16") (pintype "tri_state"))
    )
    (net (code "75") (name "unconnected-(IC6A-8Q-Pad19)") (class "Default")
      (node (ref "IC6") (pin "19") (pinfunction "8Q_19") (pintype "tri_state"))
    )
    (net (code "76") (name "unconnected-(IC7-CLK{slash}3-Pad38)") (class "Default")
      (node (ref "IC7") (pin "38") (pinfunction "CLK/3_38") (pintype "output"))
    )
    (net (code "77") (name "unconnected-(IC7-CLK{slash}24-Pad37)") (class "Default")
      (node (ref "IC7") (pin "37") (pinfunction "CLK/24_37") (pintype "output"))
    )
    (net (code "78") (name "unconnected-(IC101-IN1{slash}CLK-Pad1)") (class "Default")
      (node (ref "IC101") (pin "1") (pinfunction "IN1/CLK_1") (pintype "input"))
    )
    (net (code "79") (name "unconnected-(IC101-IN2-Pad2)") (class "Default")
      (node (ref "IC101") (pin "2") (pinfunction "IN2_2") (pintype "input"))
    )
    (net (code "80") (name "unconnected-(IC101-IN3-Pad3)") (class "Default")
      (node (ref "IC101") (pin "3") (pinfunction "IN3_3") (pintype "input"))
    )
    (net (code "81") (name "unconnected-(IC101-IN4-Pad4)") (class "Default")
      (node (ref "IC101") (pin "4") (pinfunction "IN4_4") (pintype "input"))
    )
    (net (code "82") (name "unconnected-(IC101-IO20-Pad20)") (class "Default")
      (node (ref "IC101") (pin "20") (pinfunction "IO20_20") (pintype "bidirectional"))
    )
    (net (code "83") (name "unconnected-(IC101-IO21-Pad21)") (class "Default")
      (node (ref "IC101") (pin "21") (pinfunction "IO21_21") (pintype "bidirectional"))
    )
    (net (code "84") (name "unconnected-(IC101-IO22-Pad22)") (class "Default")
      (node (ref "IC101") (pin "22") (pinfunction "IO22_22") (pintype "bidirectional"))
    )
    (net (code "85") (name "unconnected-(IC101-IO23-Pad23)") (class "Default")
      (node (ref "IC101") (pin "23") (pinfunction "IO23_23") (pintype "bidirectional"))
    )
    (net (code "86") (name "unconnected-(J301-PadSWITCH)") (class "Default")
      (node (ref "J301") (pin "SWITCH") (pinfunction "SWITCH_SWITCH") (pintype "bidirectional"))
    )
    (net (code "87") (name "unconnected-(SV101-Pad7)") (class "Default")
      (node (ref "SV101") (pin "7") (pinfunction "7_7") (pintype "passive"))
    )
    (net (code "88") (name "unconnected-(SV101-Pad8)") (class "Default")
      (node (ref "SV101") (pin "8") (pinfunction "8_8") (pintype "passive"))
    )
    (net (code "89") (name "unconnected-(SV101-Pad9)") (class "Default")
      (node (ref "SV101") (pin "9") (pinfunction "9_9") (pintype "passive"))
    )
    (net (code "90") (name "unconnected-(SV101-Pad11)") (class "Default")
      (node (ref "SV101") (pin "11") (pinfunction "11_11") (pintype "passive"))
    )
    (net (code "91") (name "unconnected-(SV101-Pad13)") (class "Default")
      (node (ref "SV101") (pin "13") (pinfunction "13_13") (pintype "passive"))
    )
    (net (code "92") (name "unconnected-(SV101-Pad14)") (class "Default")
      (node (ref "SV101") (pin "14") (pinfunction "14_14") (pintype "passive"))
    )
    (net (code "93") (name "unconnected-(SV101-Pad15)") (class "Default")
      (node (ref "SV101") (pin "15") (pinfunction "15_15") (pintype "passive"))
    )
    (net (code "94") (name "unconnected-(SV101-Pad16)") (class "Default")
      (node (ref "SV101") (pin "16") (pinfunction "16_16") (pintype "passive"))
    )
    (net (code "95") (name "unconnected-(SV101-Pad17)") (class "Default")
      (node (ref "SV101") (pin "17") (pinfunction "17_17") (pintype "passive"))
    )
    (net (code "96") (name "unconnected-(SV101-Pad18)") (class "Default")
      (node (ref "SV101") (pin "18") (pinfunction "18_18") (pintype "passive"))
    )
    (net (code "97") (name "unconnected-(SV101-Pad19)") (class "Default")
      (node (ref "SV101") (pin "19") (pinfunction "19_19") (pintype "passive"))
    )
    (net (code "98") (name "unconnected-(SV101-Pad20)") (class "Default")
      (node (ref "SV101") (pin "20") (pinfunction "20_20") (pintype "passive"))
    )
    (net (code "99") (name "unconnected-(SV101-Pad21)") (class "Default")
      (node (ref "SV101") (pin "21") (pinfunction "21_21") (pintype "passive"))
    )
    (net (code "100") (name "unconnected-(SV101-Pad22)") (class "Default")
      (node (ref "SV101") (pin "22") (pinfunction "22_22") (pintype "passive"))
    )
    (net (code "101") (name "unconnected-(SV101-Pad29)") (class "Default")
      (node (ref "SV101") (pin "29") (pinfunction "29_29") (pintype "passive"))
    )
    (net (code "102") (name "~{ATA_ACTY}") (class "Default")
      (node (ref "LED201") (pin "C") (pinfunction "C_C") (pintype "passive"))
    )
    (net (code "103") (name "~{BUS_IRQ}") (class "Default")
      (node (ref "IC101") (pin "14") (pinfunction "IO14_14") (pintype "bidirectional"))
      (node (ref "SV101") (pin "6") (pinfunction "6_6") (pintype "passive"))
    )
    (net (code "104") (name "~{SLOT_ACK}") (class "Default")
      (node (ref "IC101") (pin "15") (pinfunction "IO15_15") (pintype "bidirectional"))
      (node (ref "SV101") (pin "24") (pinfunction "24_24") (pintype "passive"))
    )
    (net (code "105") (name "~{SLOT_AS}") (class "Default")
      (node (ref "IC101") (pin "8") (pinfunction "IN8_8") (pintype "input"))
      (node (ref "SV101") (pin "32") (pinfunction "32_32") (pintype "passive"))
    )
    (net (code "106") (name "~{SLOT_CS}") (class "Default")
      (node (ref "IC101") (pin "13") (pinfunction "IN13_13") (pintype "input"))
      (node (ref "SV101") (pin "5") (pinfunction "5_5") (pintype "passive"))
    )
    (net (code "107") (name "~{SLOT_DS}") (class "Default")
      (node (ref "IC101") (pin "7") (pinfunction "IN7_7") (pintype "input"))
      (node (ref "SV101") (pin "31") (pinfunction "31_31") (pintype "passive"))
    )
    (net (code "108") (name "~{SLOT_RESET}") (class "Default")
      (node (ref "IC101") (pin "9") (pinfunction "IN9_9") (pintype "input"))
      (node (ref "SV101") (pin "30") (pinfunction "30_30") (pintype "passive"))
    )
    (net (code "109") (name "~{TMS_CAS}") (class "Default")
      (node (ref "IC4") (pin "5") (pinfunction "I_5") (pintype "input"))
      (node (ref "IC5") (pin "20") (pinfunction "~{CS}_20") (pintype "input"))
      (node (ref "IC7") (pin "2") (pinfunction "~{CAS}_2") (pintype "output"))
    )
    (net (code "110") (name "~{TMS_CS_RD}") (class "Default")
      (node (ref "IC101") (pin "18") (pinfunction "IO18_18") (pintype "bidirectional"))
      (node (ref "IC7") (pin "15") (pinfunction "~{CSR}_15") (pintype "input"))
    )
    (net (code "111") (name "~{TMS_CS_WR}") (class "Default")
      (node (ref "IC101") (pin "17") (pinfunction "IO17_17") (pintype "bidirectional"))
      (node (ref "IC7") (pin "14") (pinfunction "~{CSW}_14") (pintype "input"))
    )
    (net (code "112") (name "~{TMS_IRQ}") (class "Default")
      (node (ref "IC101") (pin "5") (pinfunction "IN5_5") (pintype "input"))
      (node (ref "IC7") (pin "16") (pinfunction "~{INT}_16") (pintype "output"))
      (node (ref "R201") (pin "1") (pinfunction "1_1") (pintype "passive"))
    )
    (net (code "113") (name "~{TMS_RAS}") (class "Default")
      (node (ref "IC4") (pin "3") (pinfunction "I_3") (pintype "input"))
      (node (ref "IC7") (pin "1") (pinfunction "~{RAS}_1") (pintype "output"))
    )
    (net (code "114") (name "~{TMS_RD}") (class "Default")
      (node (ref "IC1") (pin "11") (pinfunction "CLK_11") (pintype "input"))
      (node (ref "IC4") (pin "13") (pinfunction "I_13") (pintype "input"))
      (node (ref "IC4") (pin "2") (pinfunction "O_2") (pintype "output"))
      (node (ref "IC5") (pin "22") (pinfunction "~{OE}_22") (pintype "input"))
    )
    (net (code "115") (name "~{TMS_RESET}") (class "Default")
      (node (ref "IC101") (pin "19") (pinfunction "IO19_19") (pintype "bidirectional"))
      (node (ref "IC7") (pin "34") (pinfunction "~{RESET}_34") (pintype "input"))
    )
    (net (code "116") (name "~{TMS_WR}") (class "Default")
      (node (ref "IC4") (pin "12") (pinfunction "O_12") (pintype "output"))
    )
  )
)
